# 01_shield_stm32.net
KiCad netlist of a schematic drawn in Altium Designer
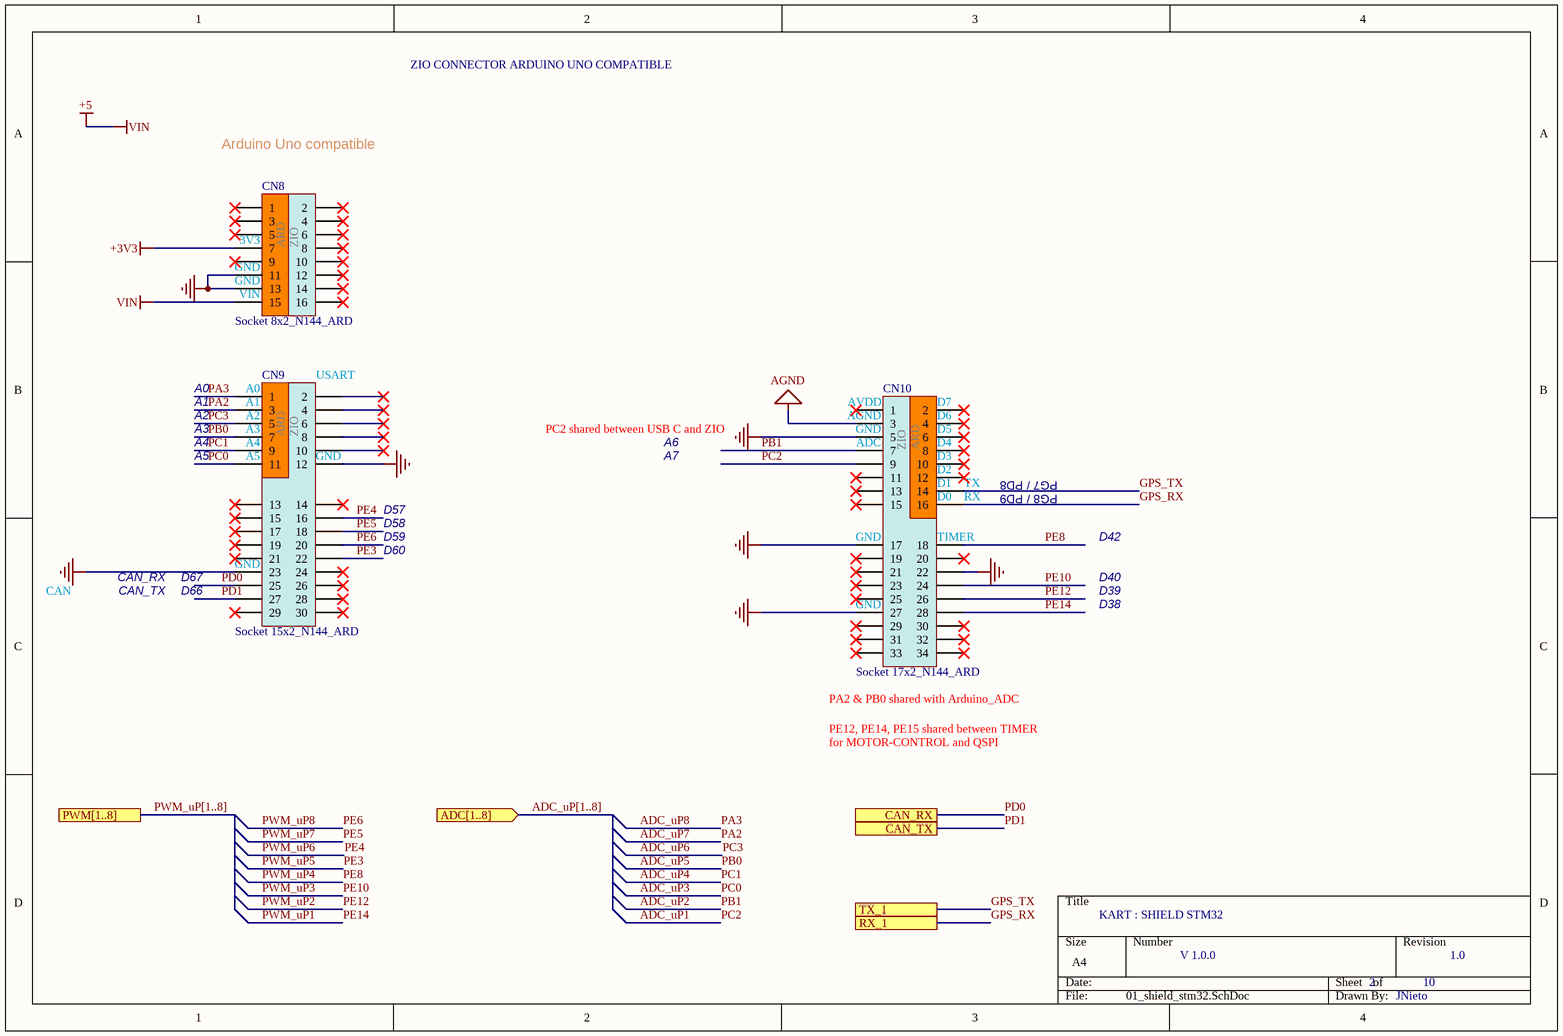
[diagram p0: 01_shield_stm32.SchDoc]

(export (version "E")
  (design (tool "Eeschema 10.0.6"))
  (components
    (comp (ref "CN8")
      (value "Socket 8x2_N144_ARD")
      (footprint "CON_SAMTEC_SSW-108-23-X-D_N144_ARD")
      (description "Socket, 8x2, 2.54mm, VR, TH, Height 8.51mm/10mm, Low insertion force.")
      (fields
        (field (name "INTERNAL_PART_NUMBER") "MCD-01037")
        (field (name "MANUFACTURER_PART_NUMBER") "SSW-108-23-x-D")
        (field (name "PROVIDED_BY") "Subcon")
      )
      (libsource (lib "MCD_PARTS_database") (part "Socket 8x2_N144_ARD"))
    )
    (comp (ref "CN9")
      (value "Socket 15x2_N144_ARD")
      (footprint "CON_SAMTEC_SSW-115-23-X-D_N144_ARD")
      (description "Socket, 15x2, 2.54mm, VR, TH, Height 8.51mm/10mm, Low insertion force.")
      (fields
        (field (name "INTERNAL_PART_NUMBER") "MCD-01040")
        (field (name "MANUFACTURER_PART_NUMBER") "SSW-115-23-x-D")
        (field (name "PROVIDED_BY") "Subcon")
      )
      (libsource (lib "MCD_PARTS_database") (part "Socket 15x2_N144_ARD"))
    )
    (comp (ref "CN10")
      (value "Socket 17x2_N144_ARD")
      (footprint "CON_SAMTEC_SSW-117-23-X-D_N144_ARD")
      (description "Socket, 17x2, 2.54mm, VR, TH, Height 8.51mm/10mm, Low insertion force")
      (fields
        (field (name "INTERNAL_PART_NUMBER") "MCD-01041")
        (field (name "MANUFACTURER_PART_NUMBER") "SSW-117-23-x-D")
        (field (name "PROVIDED_BY") "Subcon")
      )
      (libsource (lib "MCD_PARTS_database") (part "Socket 17x2_N144_ARD"))
    )
  )
  (nets
    (net (code "1") (name "+3V3") (class "Default")
      (node (ref "CN8") (pin "7") (pinfunction "7_7") (pintype "passive"))
    )
    (net (code "2") (name "+5") (class "Default")
      (node (ref "CN8") (pin "15") (pinfunction "15_15") (pintype "passive"))
    )
    (net (code "3") (name "/ADC_uP1") (class "Default")
      (node (ref "CN10") (pin "9") (pinfunction "9_9") (pintype "passive"))
    )
    (net (code "4") (name "/ADC_uP2") (class "Default")
      (node (ref "CN10") (pin "7") (pinfunction "7_7") (pintype "passive"))
    )
    (net (code "5") (name "/ADC_uP3") (class "Default")
      (node (ref "CN9") (pin "11") (pinfunction "11_11") (pintype "passive"))
    )
    (net (code "6") (name "/ADC_uP4") (class "Default")
      (node (ref "CN9") (pin "9") (pinfunction "9_9") (pintype "passive"))
    )
    (net (code "7") (name "/ADC_uP5") (class "Default")
      (node (ref "CN9") (pin "7") (pinfunction "7_7") (pintype "passive"))
    )
    (net (code "8") (name "/ADC_uP6") (class "Default")
      (node (ref "CN9") (pin "5") (pinfunction "5_5") (pintype "passive"))
    )
    (net (code "9") (name "/ADC_uP7") (class "Default")
      (node (ref "CN9") (pin "3") (pinfunction "3_3") (pintype "passive"))
    )
    (net (code "10") (name "/ADC_uP8") (class "Default")
      (node (ref "CN9") (pin "1") (pinfunction "1_1") (pintype "passive"))
    )
    (net (code "12") (name "/GPS_RX") (class "Default")
      (node (ref "CN10") (pin "16") (pinfunction "16_16") (pintype "passive"))
    )
    (net (code "13") (name "/GPS_TX") (class "Default")
      (node (ref "CN10") (pin "14") (pinfunction "14_14") (pintype "passive"))
    )
    (net (code "14") (name "/PD0") (class "Default")
      (node (ref "CN9") (pin "25") (pinfunction "25_25") (pintype "passive"))
    )
    (net (code "15") (name "/PD1") (class "Default")
      (node (ref "CN9") (pin "27") (pinfunction "27_27") (pintype "passive"))
    )
    (net (code "16") (name "/PWM_uP1") (class "Default")
      (node (ref "CN10") (pin "28") (pinfunction "28_28") (pintype "passive"))
    )
    (net (code "17") (name "/PWM_uP2") (class "Default")
      (node (ref "CN10") (pin "26") (pinfunction "26_26") (pintype "passive"))
    )
    (net (code "18") (name "/PWM_uP3") (class "Default")
      (node (ref "CN10") (pin "24") (pinfunction "24_24") (pintype "passive"))
    )
    (net (code "19") (name "/PWM_uP4") (class "Default")
      (node (ref "CN10") (pin "18") (pinfunction "18_18") (pintype "passive"))
    )
    (net (code "20") (name "/PWM_uP5") (class "Default")
      (node (ref "CN9") (pin "22") (pinfunction "22_22") (pintype "passive"))
    )
    (net (code "21") (name "/PWM_uP6") (class "Default")
      (node (ref "CN9") (pin "16") (pinfunction "16_16") (pintype "passive"))
    )
    (net (code "22") (name "/PWM_uP7") (class "Default")
      (node (ref "CN9") (pin "18") (pinfunction "18_18") (pintype "passive"))
    )
    (net (code "23") (name "/PWM_uP8") (class "Default")
      (node (ref "CN9") (pin "20") (pinfunction "20_20") (pintype "passive"))
    )
    (net (code "25") (name "AGND") (class "Default")
      (node (ref "CN10") (pin "3") (pinfunction "3_3") (pintype "passive"))
    )
    (net (code "26") (name "GND") (class "Default")
      (node (ref "CN10") (pin "17") (pinfunction "17_17") (pintype "passive"))
      (node (ref "CN10") (pin "22") (pinfunction "22_22") (pintype "passive"))
      (node (ref "CN10") (pin "27") (pinfunction "27_27") (pintype "passive"))
      (node (ref "CN10") (pin "5") (pinfunction "5_5") (pintype "passive"))
      (node (ref "CN8") (pin "11") (pinfunction "11_11") (pintype "passive"))
      (node (ref "CN8") (pin "13") (pinfunction "13_13") (pintype "passive"))
      (node (ref "CN9") (pin "12") (pinfunction "12_12") (pintype "passive"))
      (node (ref "CN9") (pin "23") (pinfunction "23_23") (pintype "passive"))
    )
    (net (code "27") (name "unconnected-(CN8-Pad1)") (class "Default")
      (node (ref "CN8") (pin "1") (pinfunction "1_1") (pintype "passive+no_connect"))
    )
    (net (code "28") (name "unconnected-(CN8-Pad2)") (class "Default")
      (node (ref "CN8") (pin "2") (pinfunction "2_2") (pintype "passive+no_connect"))
    )
    (net (code "29") (name "unconnected-(CN8-Pad3)") (class "Default")
      (node (ref "CN8") (pin "3") (pinfunction "3_3") (pintype "passive+no_connect"))
    )
    (net (code "30") (name "unconnected-(CN8-Pad4)") (class "Default")
      (node (ref "CN8") (pin "4") (pinfunction "4_4") (pintype "passive+no_connect"))
    )
    (net (code "31") (name "unconnected-(CN8-Pad5)") (class "Default")
      (node (ref "CN8") (pin "5") (pinfunction "5_5") (pintype "passive+no_connect"))
    )
    (net (code "32") (name "unconnected-(CN8-Pad6)") (class "Default")
      (node (ref "CN8") (pin "6") (pinfunction "6_6") (pintype "passive+no_connect"))
    )
    (net (code "33") (name "unconnected-(CN8-Pad8)") (class "Default")
      (node (ref "CN8") (pin "8") (pinfunction "8_8") (pintype "passive+no_connect"))
    )
    (net (code "34") (name "unconnected-(CN8-Pad9)") (class "Default")
      (node (ref "CN8") (pin "9") (pinfunction "9_9") (pintype "passive+no_connect"))
    )
    (net (code "35") (name "unconnected-(CN8-Pad10)") (class "Default")
      (node (ref "CN8") (pin "10") (pinfunction "10_10") (pintype "passive+no_connect"))
    )
    (net (code "36") (name "unconnected-(CN8-Pad12)") (class "Default")
      (node (ref "CN8") (pin "12") (pinfunction "12_12") (pintype "passive+no_connect"))
    )
    (net (code "37") (name "unconnected-(CN8-Pad14)") (class "Default")
      (node (ref "CN8") (pin "14") (pinfunction "14_14") (pintype "passive+no_connect"))
    )
    (net (code "38") (name "unconnected-(CN8-Pad16)") (class "Default")
      (node (ref "CN8") (pin "16") (pinfunction "16_16") (pintype "passive+no_connect"))
    )
    (net (code "39") (name "unconnected-(CN9-Pad2)") (class "Default")
      (node (ref "CN9") (pin "2") (pinfunction "2_2") (pintype "passive+no_connect"))
    )
    (net (code "40") (name "unconnected-(CN9-Pad4)") (class "Default")
      (node (ref "CN9") (pin "4") (pinfunction "4_4") (pintype "passive+no_connect"))
    )
    (net (code "41") (name "unconnected-(CN9-Pad6)") (class "Default")
      (node (ref "CN9") (pin "6") (pinfunction "6_6") (pintype "passive+no_connect"))
    )
    (net (code "42") (name "unconnected-(CN9-Pad8)") (class "Default")
      (node (ref "CN9") (pin "8") (pinfunction "8_8") (pintype "passive+no_connect"))
    )
    (net (code "43") (name "unconnected-(CN9-Pad10)") (class "Default")
      (node (ref "CN9") (pin "10") (pinfunction "10_10") (pintype "passive+no_connect"))
    )
    (net (code "44") (name "unconnected-(CN9-Pad13)") (class "Default")
      (node (ref "CN9") (pin "13") (pinfunction "13_13") (pintype "passive+no_connect"))
    )
    (net (code "45") (name "unconnected-(CN9-Pad14)") (class "Default")
      (node (ref "CN9") (pin "14") (pinfunction "14_14") (pintype "passive+no_connect"))
    )
    (net (code "46") (name "unconnected-(CN9-Pad15)") (class "Default")
      (node (ref "CN9") (pin "15") (pinfunction "15_15") (pintype "passive+no_connect"))
    )
    (net (code "47") (name "unconnected-(CN9-Pad17)") (class "Default")
      (node (ref "CN9") (pin "17") (pinfunction "17_17") (pintype "passive+no_connect"))
    )
    (net (code "48") (name "unconnected-(CN9-Pad19)") (class "Default")
      (node (ref "CN9") (pin "19") (pinfunction "19_19") (pintype "passive+no_connect"))
    )
    (net (code "49") (name "unconnected-(CN9-Pad21)") (class "Default")
      (node (ref "CN9") (pin "21") (pinfunction "21_21") (pintype "passive+no_connect"))
    )
    (net (code "50") (name "unconnected-(CN9-Pad24)") (class "Default")
      (node (ref "CN9") (pin "24") (pinfunction "24_24") (pintype "passive+no_connect"))
    )
    (net (code "51") (name "unconnected-(CN9-Pad26)") (class "Default")
      (node (ref "CN9") (pin "26") (pinfunction "26_26") (pintype "passive+no_connect"))
    )
    (net (code "52") (name "unconnected-(CN9-Pad28)") (class "Default")
      (node (ref "CN9") (pin "28") (pinfunction "28_28") (pintype "passive+no_connect"))
    )
    (net (code "53") (name "unconnected-(CN9-Pad29)") (class "Default")
      (node (ref "CN9") (pin "29") (pinfunction "29_29") (pintype "passive+no_connect"))
    )
    (net (code "54") (name "unconnected-(CN9-Pad30)") (class "Default")
      (node (ref "CN9") (pin "30") (pinfunction "30_30") (pintype "passive+no_connect"))
    )
    (net (code "55") (name "unconnected-(CN10-Pad1)") (class "Default")
      (node (ref "CN10") (pin "1") (pinfunction "1_1") (pintype "passive+no_connect"))
    )
    (net (code "56") (name "unconnected-(CN10-Pad2)") (class "Default")
      (node (ref "CN10") (pin "2") (pinfunction "2_2") (pintype "passive+no_connect"))
    )
    (net (code "57") (name "unconnected-(CN10-Pad4)") (class "Default")
      (node (ref "CN10") (pin "4") (pinfunction "4_4") (pintype "passive+no_connect"))
    )
    (net (code "58") (name "unconnected-(CN10-Pad6)") (class "Default")
      (node (ref "CN10") (pin "6") (pinfunction "6_6") (pintype "passive+no_connect"))
    )
    (net (code "59") (name "unconnected-(CN10-Pad8)") (class "Default")
      (node (ref "CN10") (pin "8") (pinfunction "8_8") (pintype "passive+no_connect"))
    )
    (net (code "60") (name "unconnected-(CN10-Pad10)") (class "Default")
      (node (ref "CN10") (pin "10") (pinfunction "10_10") (pintype "passive+no_connect"))
    )
    (net (code "61") (name "unconnected-(CN10-Pad11)") (class "Default")
      (node (ref "CN10") (pin "11") (pinfunction "11_11") (pintype "passive+no_connect"))
    )
    (net (code "62") (name "unconnected-(CN10-Pad12)") (class "Default")
      (node (ref "CN10") (pin "12") (pinfunction "12_12") (pintype "passive+no_connect"))
    )
    (net (code "63") (name "unconnected-(CN10-Pad13)") (class "Default")
      (node (ref "CN10") (pin "13") (pinfunction "13_13") (pintype "passive+no_connect"))
    )
    (net (code "64") (name "unconnected-(CN10-Pad15)") (class "Default")
      (node (ref "CN10") (pin "15") (pinfunction "15_15") (pintype "passive+no_connect"))
    )
    (net (code "65") (name "unconnected-(CN10-Pad19)") (class "Default")
      (node (ref "CN10") (pin "19") (pinfunction "19_19") (pintype "passive+no_connect"))
    )
    (net (code "66") (name "unconnected-(CN10-Pad20)") (class "Default")
      (node (ref "CN10") (pin "20") (pinfunction "20_20") (pintype "passive+no_connect"))
    )
    (net (code "67") (name "unconnected-(CN10-Pad21)") (class "Default")
      (node (ref "CN10") (pin "21") (pinfunction "21_21") (pintype "passive+no_connect"))
    )
    (net (code "68") (name "unconnected-(CN10-Pad23)") (class "Default")
      (node (ref "CN10") (pin "23") (pinfunction "23_23") (pintype "passive+no_connect"))
    )
    (net (code "69") (name "unconnected-(CN10-Pad25)") (class "Default")
      (node (ref "CN10") (pin "25") (pinfunction "25_25") (pintype "passive+no_connect"))
    )
    (net (code "70") (name "unconnected-(CN10-Pad29)") (class "Default")
      (node (ref "CN10") (pin "29") (pinfunction "29_29") (pintype "passive+no_connect"))
    )
    (net (code "71") (name "unconnected-(CN10-Pad30)") (class "Default")
      (node (ref "CN10") (pin "30") (pinfunction "30_30") (pintype "passive+no_connect"))
    )
    (net (code "72") (name "unconnected-(CN10-Pad31)") (class "Default")
      (node (ref "CN10") (pin "31") (pinfunction "31_31") (pintype "passive+no_connect"))
    )
    (net (code "73") (name "unconnected-(CN10-Pad32)") (class "Default")
      (node (ref "CN10") (pin "32") (pinfunction "32_32") (pintype "passive+no_connect"))
    )
    (net (code "74") (name "unconnected-(CN10-Pad33)") (class "Default")
      (node (ref "CN10") (pin "33") (pinfunction "33_33") (pintype "passive+no_connect"))
    )
    (net (code "75") (name "unconnected-(CN10-Pad34)") (class "Default")
      (node (ref "CN10") (pin "34") (pinfunction "34_34") (pintype "passive+no_connect"))
    )
  )
)
